# USB.net
KiCad netlist of a schematic drawn in Altium Designer
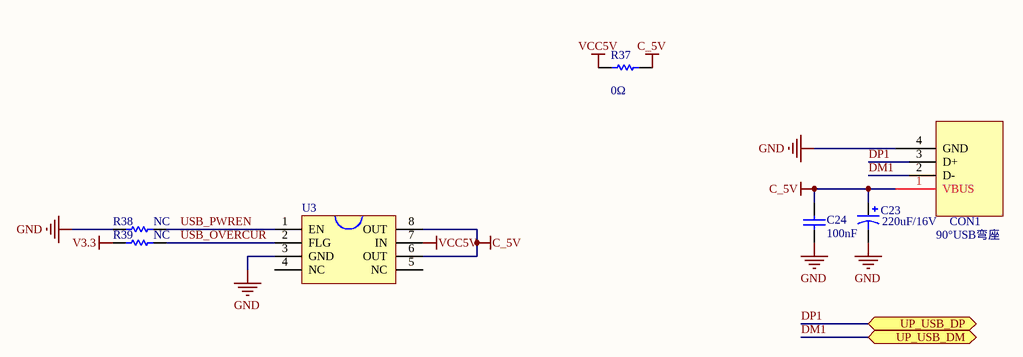
[diagram p0: USB.SchDoc]

(export (version "E")
  (design (tool "Eeschema 10.0.6"))
  (components
    (comp (ref "C23")
      (value "220uF/16V")
      (footprint "C-6032")
      (description "Polarized Capacitor (Radial)")
      (fields (field (name "PUBLISHER") "Altium Limited"))
      (libsource (lib "Miscellaneous Devices") (part "Cap Pol1"))
    )
    (comp (ref "C24") (value "100nF") (footprint "0402") (libsource (lib "CAP") (part "CAP")))
    (comp (ref "CON1")
      (value "90°USB弯座")
      (footprint "1364372")
      (libsource (lib "Interface") (part "USB-CON"))
    )
    (comp (ref "R37")
      (value "0Ω")
      (footprint "R0805N")
      (description "Semiconductor Resistor")
      (fields (field (name "PUBLISHER") "Altium Limited"))
      (libsource (lib "Miscellaneous Devices") (part "Res Semi"))
    )
    (comp (ref "R38") (value "NC") (footprint "0402") (libsource (lib "RES") (part "RES")))
    (comp (ref "R39") (value "NC") (footprint "0402") (libsource (lib "RES") (part "RES")))
    (comp (ref "U3") (value "NC") (footprint "SO8_N") (libsource (lib "Power_Charge") (part "MIC2025-1")))
  )
  (nets
    (net (code "1") (name "/DM1") (class "Default")
      (node (ref "CON1") (pin "2") (pinfunction "D-_2") (pintype "passive"))
    )
    (net (code "2") (name "/DP1") (class "Default")
      (node (ref "CON1") (pin "3") (pinfunction "D+_3") (pintype "passive"))
    )
    (net (code "3") (name "/USB_OVERCUR") (class "Default")
      (node (ref "R39") (pin "1") (pinfunction "1_1") (pintype "passive"))
      (node (ref "U3") (pin "2") (pinfunction "FLG_2") (pintype "passive"))
    )
    (net (code "4") (name "/USB_PWREN") (class "Default")
      (node (ref "R38") (pin "1") (pinfunction "1_1") (pintype "passive"))
      (node (ref "U3") (pin "1") (pinfunction "EN_1") (pintype "passive"))
    )
    (net (code "5") (name "C_5V") (class "Default")
      (node (ref "C23") (pin "1") (pinfunction "1_1") (pintype "passive"))
      (node (ref "C24") (pin "2") (pinfunction "2_2") (pintype "passive"))
      (node (ref "CON1") (pin "1") (pinfunction "VBUS_1") (pintype "passive"))
      (node (ref "R37") (pin "2") (pinfunction "2_2") (pintype "passive"))
      (node (ref "U3") (pin "6") (pinfunction "OUT_6") (pintype "passive"))
      (node (ref "U3") (pin "8") (pinfunction "OUT_8") (pintype "passive"))
    )
    (net (code "6") (name "GND") (class "Default")
      (node (ref "C23") (pin "2") (pinfunction "2_2") (pintype "passive"))
      (node (ref "C24") (pin "1") (pinfunction "1_1") (pintype "passive"))
      (node (ref "CON1") (pin "4") (pinfunction "GND_4") (pintype "passive"))
      (node (ref "R38") (pin "2") (pinfunction "2_2") (pintype "passive"))
      (node (ref "U3") (pin "3") (pinfunction "GND_3") (pintype "passive"))
    )
    (net (code "7") (name "V3.3") (class "Default")
      (node (ref "R39") (pin "2") (pinfunction "2_2") (pintype "passive"))
    )
    (net (code "8") (name "VCC5V") (class "Default")
      (node (ref "R37") (pin "1") (pinfunction "1_1") (pintype "passive"))
      (node (ref "U3") (pin "7") (pinfunction "IN_7") (pintype "passive"))
    )
    (net (code "9") (name "unconnected-(U3-NC-Pad4)") (class "Default")
      (node (ref "U3") (pin "4") (pinfunction "NC_4") (pintype "passive"))
    )
    (net (code "10") (name "unconnected-(U3-NC-Pad5)") (class "Default")
      (node (ref "U3") (pin "5") (pinfunction "NC_5") (pintype "passive"))
    )
  )
)
